# Motors_Board.net
KiCad netlist of a schematic drawn in EAGLE
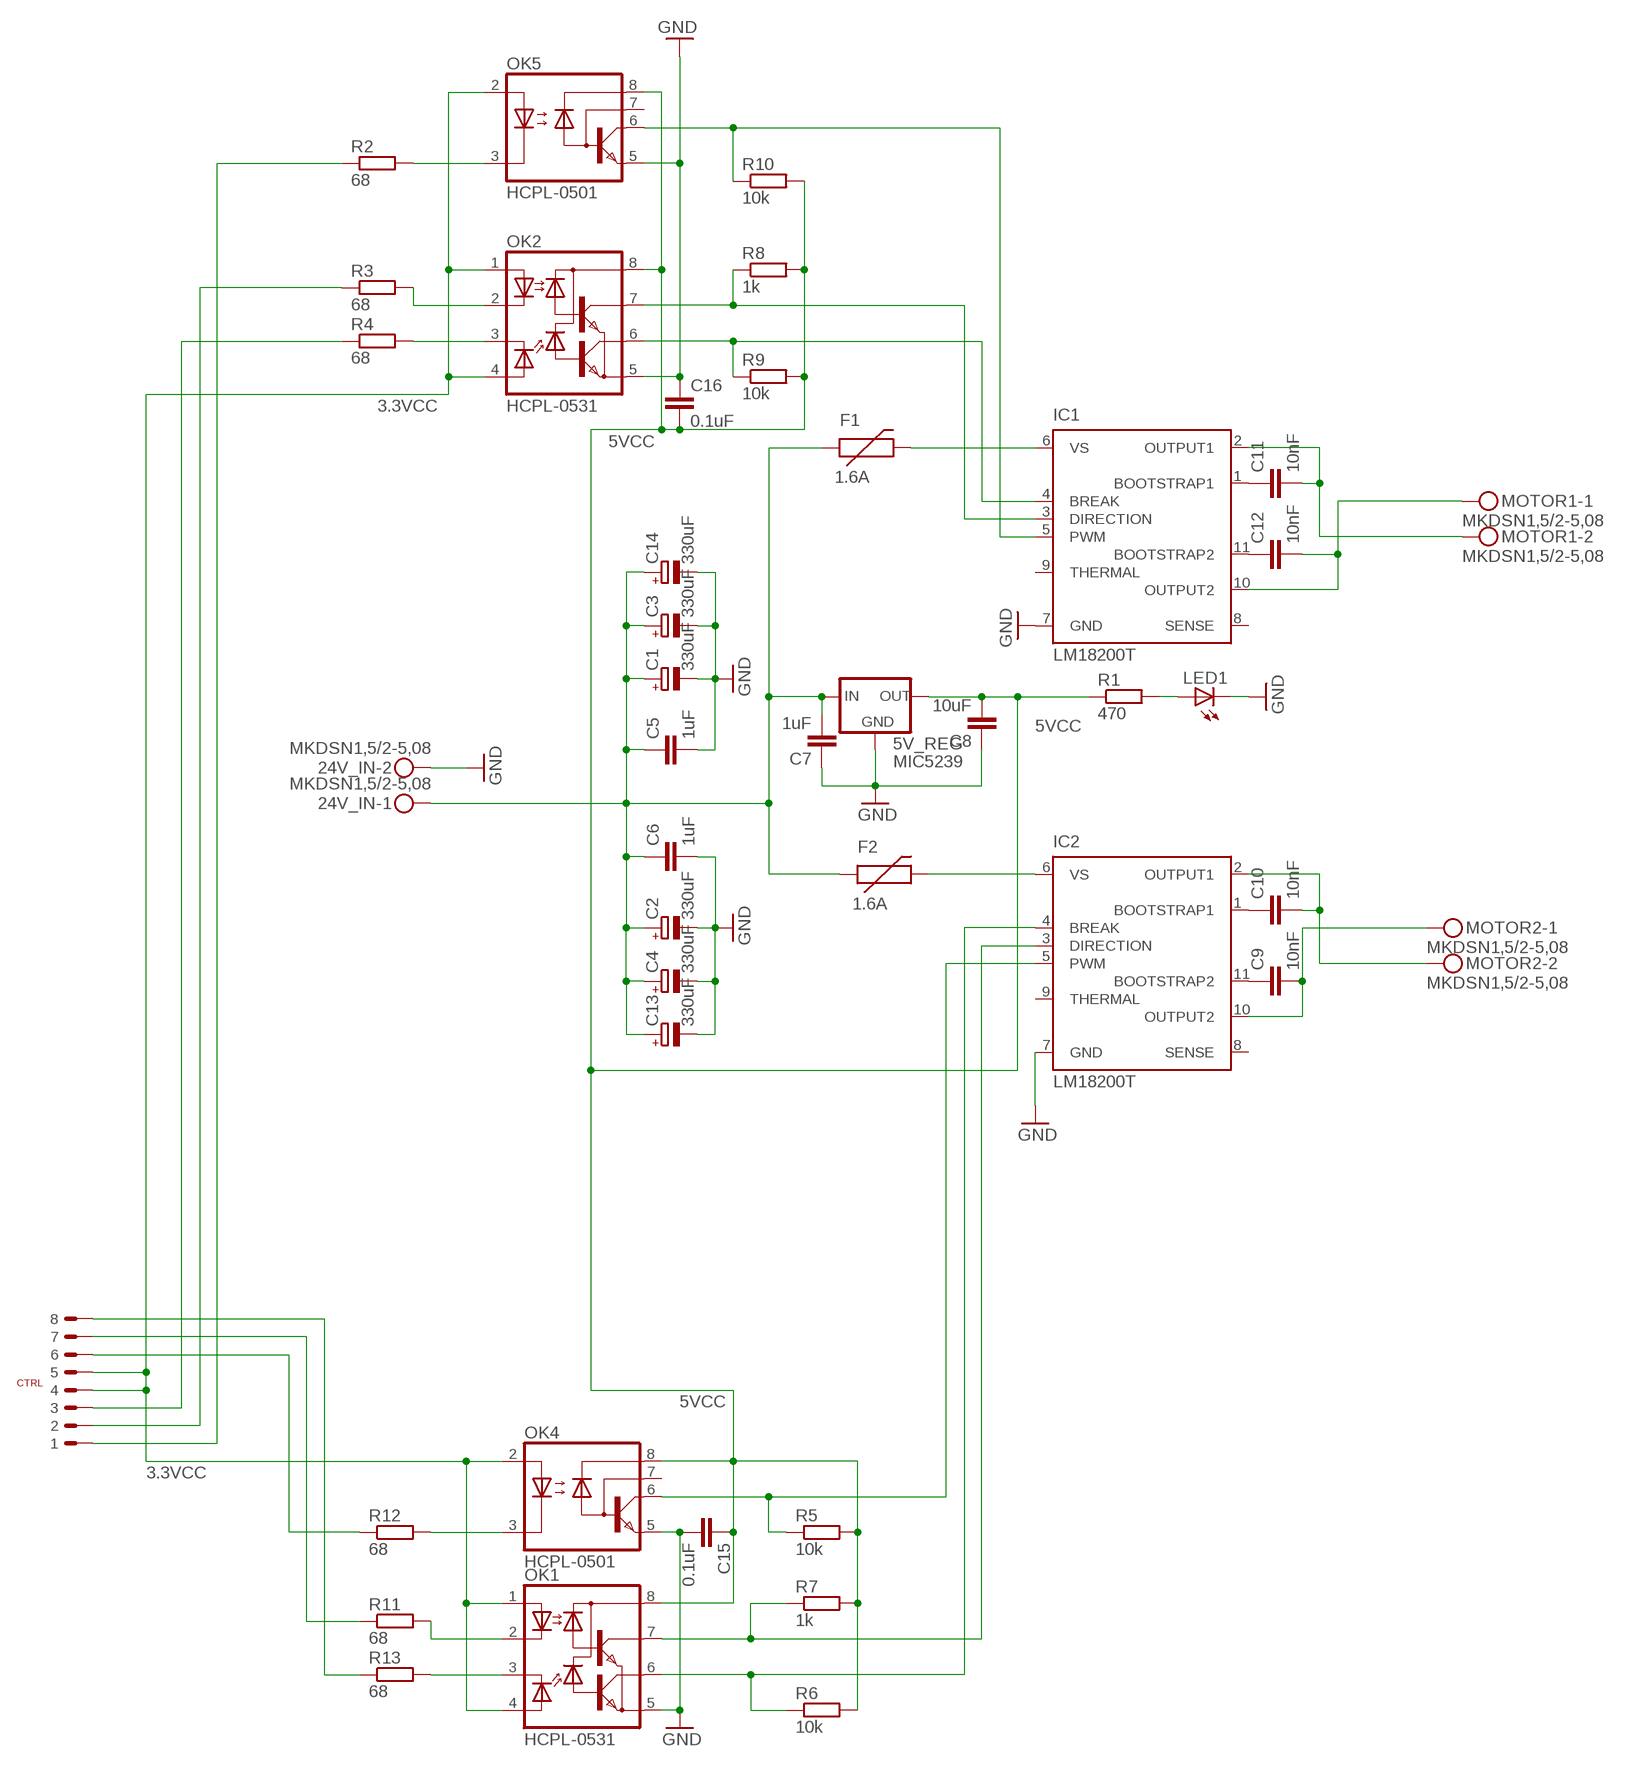
[diagram p0: schematic, sheet 1]

(export (version "E")
  (design (tool "Eeschema 10.0.6"))
  (components
    (comp (ref "5V_REG")
      (value "MIC5239")
      (footprint "eagle-import:SOT223")
      (libsource (lib "eagle-import") (part "MIC5239"))
    )
    (comp (ref "24V_IN")
      (value "MKDSN1,5/2-5,08")
      (footprint "eagle-import:MKDSN1,5_2-5,08")
      (fields (field (name "MPN") "MKDSN 1,5/2-5.08"))
      (libsource (lib "eagle-import") (part "MKDSN1,5/2-5,08"))
    )
    (comp (ref "C1")
      (value "330uF")
      (footprint "eagle-import:E5-10,5")
      (libsource (lib "eagle-import") (part "CPOL-EUE5-10.5"))
    )
    (comp (ref "C2")
      (value "330uF")
      (footprint "eagle-import:E5-10,5")
      (libsource (lib "eagle-import") (part "CPOL-EUE5-10.5"))
    )
    (comp (ref "C3")
      (value "330uF")
      (footprint "eagle-import:E5-10,5")
      (libsource (lib "eagle-import") (part "CPOL-EUE5-10.5"))
    )
    (comp (ref "C4")
      (value "330uF")
      (footprint "eagle-import:E5-10,5")
      (libsource (lib "eagle-import") (part "CPOL-EUE5-10.5"))
    )
    (comp (ref "C5")
      (value "1uF")
      (footprint "eagle-import:C1206")
      (libsource (lib "eagle-import") (part "C-EUC1206"))
    )
    (comp (ref "C6")
      (value "1uF")
      (footprint "eagle-import:C1206")
      (libsource (lib "eagle-import") (part "C-EUC1206"))
    )
    (comp (ref "C7")
      (value "1uF")
      (footprint "eagle-import:C0805")
      (libsource (lib "eagle-import") (part "C-EUC0805"))
    )
    (comp (ref "C8")
      (value "10uF")
      (footprint "eagle-import:C0805")
      (libsource (lib "eagle-import") (part "C-EUC0805"))
    )
    (comp (ref "C9")
      (value "10nF")
      (footprint "eagle-import:C0603")
      (libsource (lib "eagle-import") (part "C-EUC0603"))
    )
    (comp (ref "C10")
      (value "10nF")
      (footprint "eagle-import:C0603")
      (libsource (lib "eagle-import") (part "C-EUC0603"))
    )
    (comp (ref "C11")
      (value "10nF")
      (footprint "eagle-import:C0603")
      (libsource (lib "eagle-import") (part "C-EUC0603"))
    )
    (comp (ref "C12")
      (value "10nF")
      (footprint "eagle-import:C0603")
      (libsource (lib "eagle-import") (part "C-EUC0603"))
    )
    (comp (ref "C13")
      (value "330uF")
      (footprint "eagle-import:E5-10,5")
      (libsource (lib "eagle-import") (part "CPOL-EUE5-10.5"))
    )
    (comp (ref "C14")
      (value "330uF")
      (footprint "eagle-import:E5-10,5")
      (libsource (lib "eagle-import") (part "CPOL-EUE5-10.5"))
    )
    (comp (ref "C15")
      (value "0.1uF")
      (footprint "eagle-import:C0603")
      (libsource (lib "eagle-import") (part "C-EUC0603"))
    )
    (comp (ref "C16")
      (value "0.1uF")
      (footprint "eagle-import:C0603")
      (libsource (lib "eagle-import") (part "C-EUC0603"))
    )
    (comp (ref "CTRL")
      (value "87437-0843")
      (footprint "eagle-import:87437-0843")
      (libsource (lib "eagle-import") (part "87437-0843"))
    )
    (comp (ref "F1")
      (value "1.6A")
      (footprint "eagle-import:PTC")
      (libsource (lib "eagle-import") (part "PTCPTH"))
    )
    (comp (ref "F2")
      (value "1.6A")
      (footprint "eagle-import:PTC")
      (libsource (lib "eagle-import") (part "PTCPTH"))
    )
    (comp (ref "IC1")
      (value "LM18200T")
      (footprint "eagle-import:TO-220-11")
      (libsource (lib "eagle-import") (part "LM18200T"))
    )
    (comp (ref "IC2")
      (value "LM18200T")
      (footprint "eagle-import:TO-220-11")
      (libsource (lib "eagle-import") (part "LM18200T"))
    )
    (comp (ref "LED1")
      (value "LEDCHIP-LED0603")
      (footprint "eagle-import:CHIP-LED0603")
      (libsource (lib "eagle-import") (part "LEDCHIP-LED0603"))
    )
    (comp (ref "MOTOR1")
      (value "MKDSN1,5/2-5,08")
      (footprint "eagle-import:MKDSN1,5_2-5,08")
      (fields (field (name "MPN") "MKDSN 1,5/2-5.08"))
      (libsource (lib "eagle-import") (part "MKDSN1,5/2-5,08"))
    )
    (comp (ref "MOTOR2")
      (value "MKDSN1,5/2-5,08")
      (footprint "eagle-import:MKDSN1,5_2-5,08")
      (fields (field (name "MPN") "MKDSN 1,5/2-5.08"))
      (libsource (lib "eagle-import") (part "MKDSN1,5/2-5,08"))
    )
    (comp (ref "OK1")
      (value "HCPL-0531")
      (footprint "eagle-import:SOIC8")
      (libsource (lib "eagle-import") (part "HCPL-0531"))
    )
    (comp (ref "OK2")
      (value "HCPL-0531")
      (footprint "eagle-import:SOIC8")
      (libsource (lib "eagle-import") (part "HCPL-0531"))
    )
    (comp (ref "OK4")
      (value "HCPL-0501")
      (footprint "eagle-import:SOIC08")
      (fields (field (name "MF") "AGILENT TECHNOLOGIES") (field (name "MPN") "HCPL-0500-000E"))
      (libsource (lib "eagle-import") (part "HCPL0500"))
    )
    (comp (ref "OK5")
      (value "HCPL-0501")
      (footprint "eagle-import:SOIC08")
      (fields (field (name "MF") "AGILENT TECHNOLOGIES") (field (name "MPN") "HCPL-0500-000E"))
      (libsource (lib "eagle-import") (part "HCPL0500"))
    )
    (comp (ref "R1")
      (value "470")
      (footprint "eagle-import:R0603")
      (libsource (lib "eagle-import") (part "R-EU_R0603"))
    )
    (comp (ref "R2")
      (value "68")
      (footprint "eagle-import:R0603")
      (libsource (lib "eagle-import") (part "R-EU_R0603"))
    )
    (comp (ref "R3")
      (value "68")
      (footprint "eagle-import:R0603")
      (libsource (lib "eagle-import") (part "R-EU_R0603"))
    )
    (comp (ref "R4")
      (value "68")
      (footprint "eagle-import:R0603")
      (libsource (lib "eagle-import") (part "R-EU_R0603"))
    )
    (comp (ref "R5")
      (value "10k")
      (footprint "eagle-import:R0603")
      (libsource (lib "eagle-import") (part "R-EU_R0603"))
    )
    (comp (ref "R6")
      (value "10k")
      (footprint "eagle-import:R0603")
      (libsource (lib "eagle-import") (part "R-EU_R0603"))
    )
    (comp (ref "R7")
      (value "1k")
      (footprint "eagle-import:R0603")
      (libsource (lib "eagle-import") (part "R-EU_R0603"))
    )
    (comp (ref "R8")
      (value "1k")
      (footprint "eagle-import:R0603")
      (libsource (lib "eagle-import") (part "R-EU_R0603"))
    )
    (comp (ref "R9")
      (value "10k")
      (footprint "eagle-import:R0603")
      (libsource (lib "eagle-import") (part "R-EU_R0603"))
    )
    (comp (ref "R10")
      (value "10k")
      (footprint "eagle-import:R0603")
      (libsource (lib "eagle-import") (part "R-EU_R0603"))
    )
    (comp (ref "R11")
      (value "68")
      (footprint "eagle-import:R0603")
      (libsource (lib "eagle-import") (part "R-EU_R0603"))
    )
    (comp (ref "R12")
      (value "68")
      (footprint "eagle-import:R0603")
      (libsource (lib "eagle-import") (part "R-EU_R0603"))
    )
    (comp (ref "R13")
      (value "68")
      (footprint "eagle-import:R0603")
      (libsource (lib "eagle-import") (part "R-EU_R0603"))
    )
  )
  (nets
    (net (code "1") (name "/3.3VCC") (class "Default")
      (node (ref "CTRL") (pin "P$4") (pinfunction "4_P$4") (pintype "bidirectional"))
      (node (ref "CTRL") (pin "P$5") (pinfunction "5_P$5") (pintype "bidirectional"))
      (node (ref "OK1") (pin "1") (pinfunction "A1_1") (pintype "passive"))
      (node (ref "OK1") (pin "4") (pinfunction "A2_4") (pintype "passive"))
      (node (ref "OK2") (pin "1") (pinfunction "A1_1") (pintype "passive"))
      (node (ref "OK2") (pin "4") (pinfunction "A2_4") (pintype "passive"))
      (node (ref "OK4") (pin "2") (pinfunction "A_2") (pintype "passive"))
      (node (ref "OK5") (pin "2") (pinfunction "A_2") (pintype "passive"))
    )
    (net (code "2") (name "/5VCC") (class "Default")
      (node (ref "5V_REG") (pin "3") (pinfunction "OUT_3") (pintype "passive"))
      (node (ref "C15") (pin "1") (pinfunction "1_1") (pintype "passive"))
      (node (ref "C16") (pin "2") (pinfunction "2_2") (pintype "passive"))
      (node (ref "C8") (pin "2") (pinfunction "2_2") (pintype "passive"))
      (node (ref "OK1") (pin "8") (pinfunction "VCC_8") (pintype "passive"))
      (node (ref "OK2") (pin "8") (pinfunction "VCC_8") (pintype "passive"))
      (node (ref "OK4") (pin "8") (pinfunction "VCC_8") (pintype "passive"))
      (node (ref "OK5") (pin "8") (pinfunction "VCC_8") (pintype "passive"))
      (node (ref "R1") (pin "1") (pinfunction "1_1") (pintype "passive"))
      (node (ref "R10") (pin "2") (pinfunction "2_2") (pintype "passive"))
      (node (ref "R5") (pin "2") (pinfunction "2_2") (pintype "passive"))
      (node (ref "R6") (pin "2") (pinfunction "2_2") (pintype "passive"))
      (node (ref "R7") (pin "2") (pinfunction "2_2") (pintype "passive"))
      (node (ref "R8") (pin "2") (pinfunction "2_2") (pintype "passive"))
      (node (ref "R9") (pin "2") (pinfunction "2_2") (pintype "passive"))
    )
    (net (code "3") (name "GND") (class "Default")
      (node (ref "24V_IN") (pin "2") (pinfunction "KL_2") (pintype "passive"))
      (node (ref "5V_REG") (pin "2") (pinfunction "GND_2") (pintype "input"))
      (node (ref "5V_REG") (pin "4") (pinfunction "GND_4") (pintype "input"))
      (node (ref "C1") (pin "-") (pinfunction "-_-") (pintype "passive"))
      (node (ref "C13") (pin "-") (pinfunction "-_-") (pintype "passive"))
      (node (ref "C14") (pin "-") (pinfunction "-_-") (pintype "passive"))
      (node (ref "C15") (pin "2") (pinfunction "2_2") (pintype "passive"))
      (node (ref "C16") (pin "1") (pinfunction "1_1") (pintype "passive"))
      (node (ref "C2") (pin "-") (pinfunction "-_-") (pintype "passive"))
      (node (ref "C3") (pin "-") (pinfunction "-_-") (pintype "passive"))
      (node (ref "C4") (pin "-") (pinfunction "-_-") (pintype "passive"))
      (node (ref "C5") (pin "2") (pinfunction "2_2") (pintype "passive"))
      (node (ref "C6") (pin "2") (pinfunction "2_2") (pintype "passive"))
      (node (ref "C7") (pin "1") (pinfunction "1_1") (pintype "passive"))
      (node (ref "C8") (pin "1") (pinfunction "1_1") (pintype "passive"))
      (node (ref "IC1") (pin "7") (pinfunction "GND_7") (pintype "power_in"))
      (node (ref "IC2") (pin "7") (pinfunction "GND_7") (pintype "power_in"))
      (node (ref "LED1") (pin "C") (pinfunction "C_C") (pintype "passive"))
      (node (ref "OK1") (pin "5") (pinfunction "GND_5") (pintype "passive"))
      (node (ref "OK2") (pin "5") (pinfunction "GND_5") (pintype "passive"))
      (node (ref "OK4") (pin "5") (pinfunction "GND_5") (pintype "passive"))
      (node (ref "OK5") (pin "5") (pinfunction "GND_5") (pintype "passive"))
    )
    (net (code "4") (name "Net-(24V_INA-KL)") (class "Default")
      (node (ref "24V_IN") (pin "1") (pinfunction "KL_1") (pintype "passive"))
      (node (ref "5V_REG") (pin "1") (pinfunction "IN_1") (pintype "input"))
      (node (ref "C1") (pin "+") (pinfunction "+_+") (pintype "passive"))
      (node (ref "C13") (pin "+") (pinfunction "+_+") (pintype "passive"))
      (node (ref "C14") (pin "+") (pinfunction "+_+") (pintype "passive"))
      (node (ref "C2") (pin "+") (pinfunction "+_+") (pintype "passive"))
      (node (ref "C3") (pin "+") (pinfunction "+_+") (pintype "passive"))
      (node (ref "C4") (pin "+") (pinfunction "+_+") (pintype "passive"))
      (node (ref "C5") (pin "1") (pinfunction "1_1") (pintype "passive"))
      (node (ref "C6") (pin "1") (pinfunction "1_1") (pintype "passive"))
      (node (ref "C7") (pin "2") (pinfunction "2_2") (pintype "passive"))
      (node (ref "F1") (pin "P$1") (pinfunction "1_P$1") (pintype "bidirectional"))
      (node (ref "F2") (pin "P$1") (pinfunction "1_P$1") (pintype "bidirectional"))
    )
    (net (code "5") (name "Net-(CTRL-1)") (class "Default")
      (node (ref "CTRL") (pin "P$1") (pinfunction "1_P$1") (pintype "bidirectional"))
      (node (ref "R2") (pin "1") (pinfunction "1_1") (pintype "passive"))
    )
    (net (code "6") (name "Net-(CTRL-2)") (class "Default")
      (node (ref "CTRL") (pin "P$2") (pinfunction "2_P$2") (pintype "bidirectional"))
      (node (ref "R3") (pin "1") (pinfunction "1_1") (pintype "passive"))
    )
    (net (code "7") (name "Net-(CTRL-3)") (class "Default")
      (node (ref "CTRL") (pin "P$3") (pinfunction "3_P$3") (pintype "bidirectional"))
      (node (ref "R4") (pin "1") (pinfunction "1_1") (pintype "passive"))
    )
    (net (code "8") (name "Net-(CTRL-6)") (class "Default")
      (node (ref "CTRL") (pin "P$6") (pinfunction "6_P$6") (pintype "bidirectional"))
      (node (ref "R12") (pin "1") (pinfunction "1_1") (pintype "passive"))
    )
    (net (code "9") (name "Net-(CTRL-7)") (class "Default")
      (node (ref "CTRL") (pin "P$7") (pinfunction "7_P$7") (pintype "bidirectional"))
      (node (ref "R11") (pin "1") (pinfunction "1_1") (pintype "passive"))
    )
    (net (code "10") (name "Net-(CTRL-8)") (class "Default")
      (node (ref "CTRL") (pin "P$8") (pinfunction "8_P$8") (pintype "bidirectional"))
      (node (ref "R13") (pin "1") (pinfunction "1_1") (pintype "passive"))
    )
    (net (code "11") (name "Net-(F1-2)") (class "Default")
      (node (ref "F1") (pin "P$2") (pinfunction "2_P$2") (pintype "bidirectional"))
      (node (ref "IC1") (pin "6") (pinfunction "VS_6") (pintype "power_in"))
    )
    (net (code "12") (name "Net-(F2-2)") (class "Default")
      (node (ref "F2") (pin "P$2") (pinfunction "2_P$2") (pintype "bidirectional"))
      (node (ref "IC2") (pin "6") (pinfunction "VS_6") (pintype "power_in"))
    )
    (net (code "13") (name "Net-(IC1-BOOTSTRAP1)") (class "Default")
      (node (ref "C11") (pin "1") (pinfunction "1_1") (pintype "passive"))
      (node (ref "IC1") (pin "1") (pinfunction "BOOTSTRAP1_1") (pintype "input"))
    )
    (net (code "14") (name "Net-(IC1-BOOTSTRAP2)") (class "Default")
      (node (ref "C12") (pin "1") (pinfunction "1_1") (pintype "passive"))
      (node (ref "IC1") (pin "11") (pinfunction "BOOTSTRAP2_11") (pintype "input"))
    )
    (net (code "15") (name "Net-(IC1-BREAK)") (class "Default")
      (node (ref "IC1") (pin "4") (pinfunction "BREAK_4") (pintype "input"))
      (node (ref "OK2") (pin "6") (pinfunction "VO2_6") (pintype "passive"))
      (node (ref "R9") (pin "1") (pinfunction "1_1") (pintype "passive"))
    )
    (net (code "16") (name "Net-(IC1-DIRECTION)") (class "Default")
      (node (ref "IC1") (pin "3") (pinfunction "DIRECTION_3") (pintype "input"))
      (node (ref "OK2") (pin "7") (pinfunction "VO1_7") (pintype "passive"))
      (node (ref "R8") (pin "1") (pinfunction "1_1") (pintype "passive"))
    )
    (net (code "17") (name "Net-(IC1-OUTPUT1)") (class "Default")
      (node (ref "C11") (pin "2") (pinfunction "2_2") (pintype "passive"))
      (node (ref "IC1") (pin "2") (pinfunction "OUTPUT1_2") (pintype "output"))
      (node (ref "MOTOR1") (pin "2") (pinfunction "KL_2") (pintype "passive"))
    )
    (net (code "18") (name "Net-(IC1-OUTPUT2)") (class "Default")
      (node (ref "C12") (pin "2") (pinfunction "2_2") (pintype "passive"))
      (node (ref "IC1") (pin "10") (pinfunction "OUTPUT2_10") (pintype "output"))
      (node (ref "MOTOR1") (pin "1") (pinfunction "KL_1") (pintype "passive"))
    )
    (net (code "19") (name "Net-(IC1-PWM)") (class "Default")
      (node (ref "IC1") (pin "5") (pinfunction "PWM_5") (pintype "input"))
      (node (ref "OK5") (pin "6") (pinfunction "VO_6") (pintype "passive"))
      (node (ref "R10") (pin "1") (pinfunction "1_1") (pintype "passive"))
    )
    (net (code "20") (name "Net-(IC2-BOOTSTRAP1)") (class "Default")
      (node (ref "C10") (pin "1") (pinfunction "1_1") (pintype "passive"))
      (node (ref "IC2") (pin "1") (pinfunction "BOOTSTRAP1_1") (pintype "input"))
    )
    (net (code "21") (name "Net-(IC2-BOOTSTRAP2)") (class "Default")
      (node (ref "C9") (pin "1") (pinfunction "1_1") (pintype "passive"))
      (node (ref "IC2") (pin "11") (pinfunction "BOOTSTRAP2_11") (pintype "input"))
    )
    (net (code "22") (name "Net-(IC2-BREAK)") (class "Default")
      (node (ref "IC2") (pin "4") (pinfunction "BREAK_4") (pintype "input"))
      (node (ref "OK1") (pin "6") (pinfunction "VO2_6") (pintype "passive"))
      (node (ref "R6") (pin "1") (pinfunction "1_1") (pintype "passive"))
    )
    (net (code "23") (name "Net-(IC2-DIRECTION)") (class "Default")
      (node (ref "IC2") (pin "3") (pinfunction "DIRECTION_3") (pintype "input"))
      (node (ref "OK1") (pin "7") (pinfunction "VO1_7") (pintype "passive"))
      (node (ref "R7") (pin "1") (pinfunction "1_1") (pintype "passive"))
    )
    (net (code "24") (name "Net-(IC2-OUTPUT1)") (class "Default")
      (node (ref "C10") (pin "2") (pinfunction "2_2") (pintype "passive"))
      (node (ref "IC2") (pin "2") (pinfunction "OUTPUT1_2") (pintype "output"))
      (node (ref "MOTOR2") (pin "2") (pinfunction "KL_2") (pintype "passive"))
    )
    (net (code "25") (name "Net-(IC2-OUTPUT2)") (class "Default")
      (node (ref "C9") (pin "2") (pinfunction "2_2") (pintype "passive"))
      (node (ref "IC2") (pin "10") (pinfunction "OUTPUT2_10") (pintype "output"))
      (node (ref "MOTOR2") (pin "1") (pinfunction "KL_1") (pintype "passive"))
    )
    (net (code "26") (name "Net-(IC2-PWM)") (class "Default")
      (node (ref "IC2") (pin "5") (pinfunction "PWM_5") (pintype "input"))
      (node (ref "OK4") (pin "6") (pinfunction "VO_6") (pintype "passive"))
      (node (ref "R5") (pin "1") (pinfunction "1_1") (pintype "passive"))
    )
    (net (code "27") (name "Net-(LED1-PadA)") (class "Default")
      (node (ref "LED1") (pin "A") (pinfunction "A_A") (pintype "passive"))
      (node (ref "R1") (pin "2") (pinfunction "2_2") (pintype "passive"))
    )
    (net (code "28") (name "Net-(OK1-C1)") (class "Default")
      (node (ref "OK1") (pin "2") (pinfunction "C1_2") (pintype "passive"))
      (node (ref "R11") (pin "2") (pinfunction "2_2") (pintype "passive"))
    )
    (net (code "29") (name "Net-(OK1-C2)") (class "Default")
      (node (ref "OK1") (pin "3") (pinfunction "C2_3") (pintype "passive"))
      (node (ref "R13") (pin "2") (pinfunction "2_2") (pintype "passive"))
    )
    (net (code "30") (name "Net-(OK2-C1)") (class "Default")
      (node (ref "OK2") (pin "2") (pinfunction "C1_2") (pintype "passive"))
      (node (ref "R3") (pin "2") (pinfunction "2_2") (pintype "passive"))
    )
    (net (code "31") (name "Net-(OK2-C2)") (class "Default")
      (node (ref "OK2") (pin "3") (pinfunction "C2_3") (pintype "passive"))
      (node (ref "R4") (pin "2") (pinfunction "2_2") (pintype "passive"))
    )
    (net (code "32") (name "Net-(OK4-C)") (class "Default")
      (node (ref "OK4") (pin "3") (pinfunction "C_3") (pintype "passive"))
      (node (ref "R12") (pin "2") (pinfunction "2_2") (pintype "passive"))
    )
    (net (code "33") (name "Net-(OK5-C)") (class "Default")
      (node (ref "OK5") (pin "3") (pinfunction "C_3") (pintype "passive"))
      (node (ref "R2") (pin "2") (pinfunction "2_2") (pintype "passive"))
    )
    (net (code "34") (name "unconnected-(IC1-SENSE-Pad8)") (class "Default")
      (node (ref "IC1") (pin "8") (pinfunction "SENSE_8") (pintype "output"))
    )
    (net (code "35") (name "unconnected-(IC1-THERMAL-Pad9)") (class "Default")
      (node (ref "IC1") (pin "9") (pinfunction "THERMAL_9") (pintype "output"))
    )
    (net (code "36") (name "unconnected-(IC2-SENSE-Pad8)") (class "Default")
      (node (ref "IC2") (pin "8") (pinfunction "SENSE_8") (pintype "output"))
    )
    (net (code "37") (name "unconnected-(IC2-THERMAL-Pad9)") (class "Default")
      (node (ref "IC2") (pin "9") (pinfunction "THERMAL_9") (pintype "output"))
    )
    (net (code "38") (name "unconnected-(OK4-VB-Pad7)") (class "Default")
      (node (ref "OK4") (pin "7") (pinfunction "VB_7") (pintype "passive"))
    )
    (net (code "39") (name "unconnected-(OK5-VB-Pad7)") (class "Default")
      (node (ref "OK5") (pin "7") (pinfunction "VB_7") (pintype "passive"))
    )
  )
)
